# 04_FPGA_Bank500_Bank501.net
KiCad netlist of a schematic drawn in Altium Designer
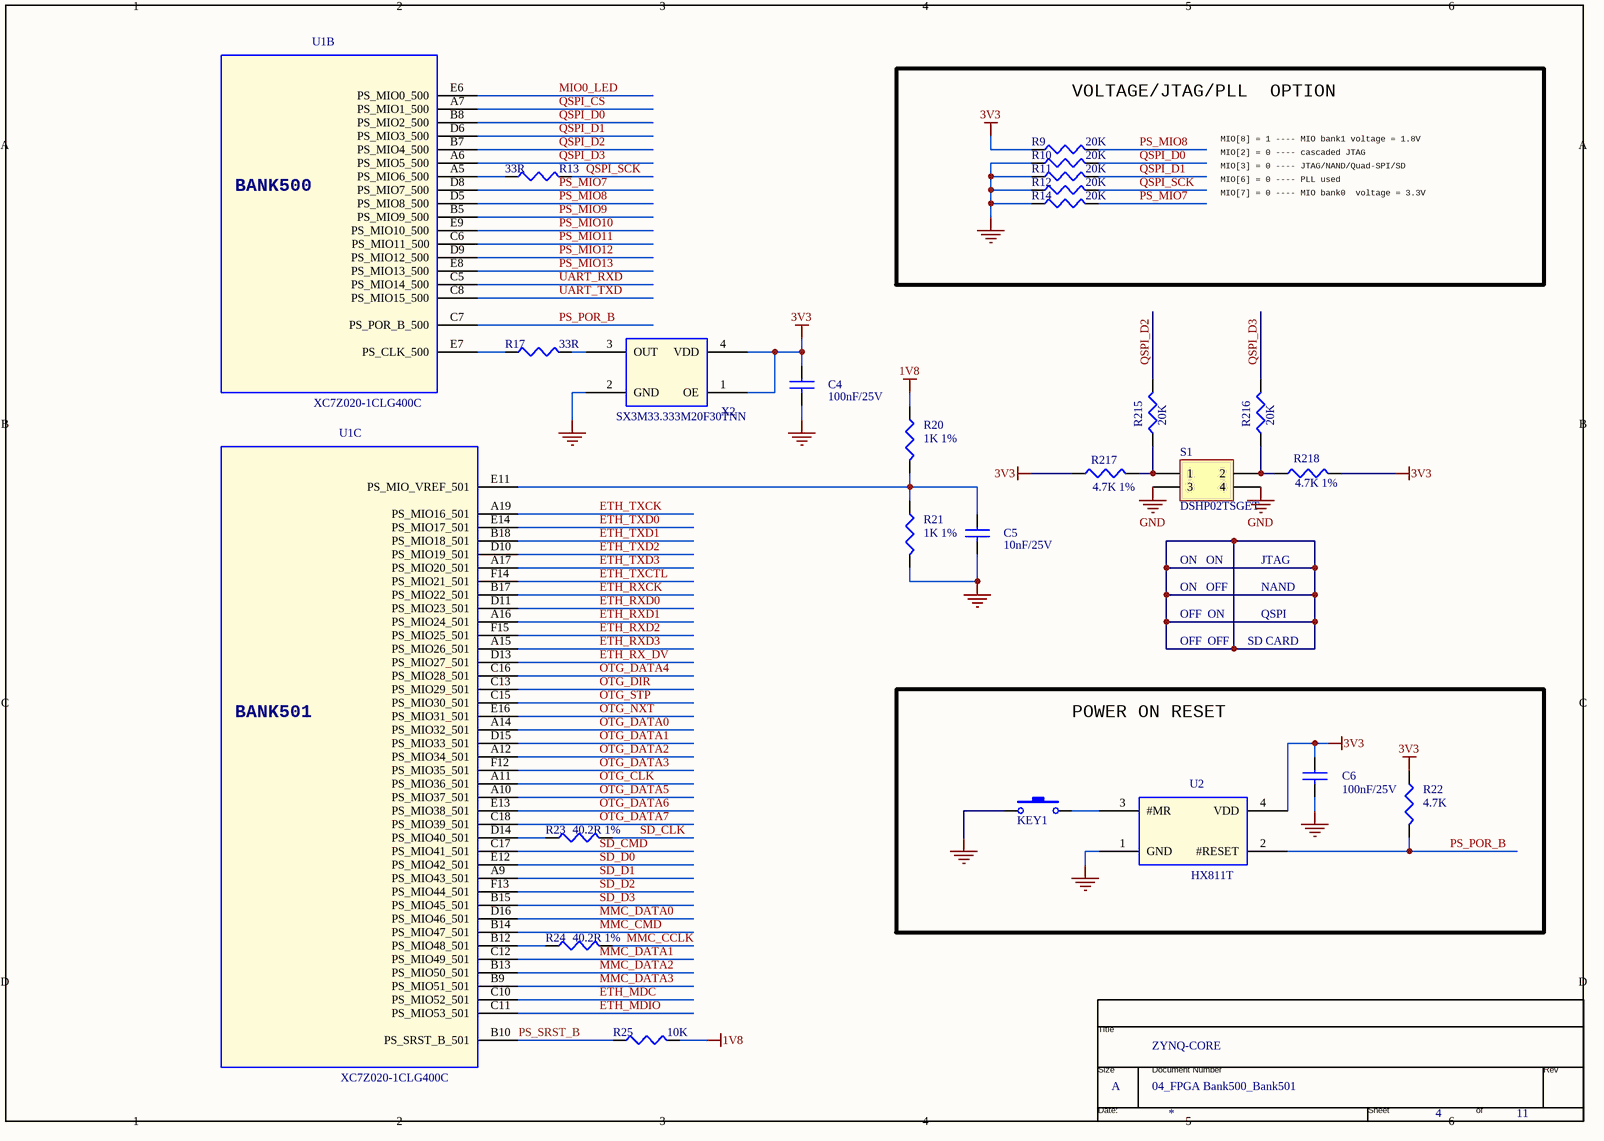
[diagram p0: 04_FPGA Bank500_Bank501.SchDoc]

(export (version "E")
  (design (tool "Eeschema 10.0.6"))
  (components
    (comp (ref "C4") (value "100nF/25V") (footprint "C0402") (libsource (lib "*") (part "CAP NP_Dup1")))
    (comp (ref "C5") (value "10nF/25V") (footprint "C0402") (libsource (lib "*") (part "CAP NP_Dup1")))
    (comp (ref "C6") (value "100nF/25V") (footprint "C0402") (libsource (lib "*") (part "CAP NP_Dup1")))
    (comp (ref "KEY1")
      (value "TS-1071AD-A1B3-D4")
      (footprint "KEY_3*4*2")
      (libsource (lib "AD库工程--FEIGE") (part "switch-anniu"))
    )
    (comp (ref "R9") (value "20K") (footprint "R0402") (libsource (lib "*") (part "RESISTOR_Dup1")))
    (comp (ref "R10") (value "20K") (footprint "R0402") (libsource (lib "*") (part "RESISTOR_Dup1")))
    (comp (ref "R11") (value "20K") (footprint "R0402") (libsource (lib "*") (part "RESISTOR_Dup1")))
    (comp (ref "R12") (value "20K") (footprint "R0402") (libsource (lib "*") (part "RESISTOR_Dup1")))
    (comp (ref "R13") (value "33R") (footprint "R0402") (libsource (lib "*") (part "RESISTOR_Dup1")))
    (comp (ref "R14") (value "20K") (footprint "R0402") (libsource (lib "*") (part "RESISTOR_Dup1")))
    (comp (ref "R17") (value "33R") (footprint "R0402") (libsource (lib "*") (part "RESISTOR_Dup1")))
    (comp (ref "R20") (value "1K 1%") (footprint "R0402") (libsource (lib "*") (part "RESISTOR_Dup1")))
    (comp (ref "R21") (value "1K 1%") (footprint "R0402") (libsource (lib "*") (part "RESISTOR_Dup1")))
    (comp (ref "R22") (value "4.7K") (footprint "R0402") (libsource (lib "*") (part "RESISTOR_Dup1")))
    (comp (ref "R23") (value "40.2R 1%") (footprint "R0402") (libsource (lib "*") (part "RESISTOR_Dup1")))
    (comp (ref "R24") (value "40.2R 1%") (footprint "R0402") (libsource (lib "*") (part "RESISTOR_Dup1")))
    (comp (ref "R25") (value "10K") (footprint "R0402") (libsource (lib "*") (part "RESISTOR_Dup1")))
    (comp (ref "R215") (value "20K") (footprint "R0402") (libsource (lib "*") (part "RESISTOR_Dup1")))
    (comp (ref "R216") (value "20K") (footprint "R0402") (libsource (lib "*") (part "RESISTOR_Dup1")))
    (comp (ref "R217") (value "4.7K 1%") (footprint "R0402") (libsource (lib "*") (part "RESISTOR_Dup1")))
    (comp (ref "R218") (value "4.7K 1%") (footprint "R0402") (libsource (lib "*") (part "RESISTOR_Dup1")))
    (comp (ref "S1")
      (value "DSHP02TSGET")
      (footprint "KE-1.27-2Pin")
      (description "拨码开关")
      (fields (field (name "PUBLISHER") "Altium Limited"))
      (libsource (lib "Miscellaneous Connectors") (part "Header 2X2"))
    )
    (comp (ref "U1")
      (value "XC7Z020-1CLG400C")
      (footprint "CLG400")
      (libsource (lib "*") (part "Zynq7010/7020"))
    )
    (comp (ref "U2") (value "HX811T") (footprint "TCM811TERCTR") (libsource (lib "*") (part "TCM811TERCTR")))
    (comp (ref "X2")
      (value "SX3M33.333M20F30TNN")
      (footprint "OSC3_2X2_5")
      (libsource (lib "*") (part "crystal_active"))
    )
  )
  (nets
    (net (code "1") (name "/ETH_MDC") (class "Default")
      (node (ref "U1") (pin "C10") (pinfunction "PS_MIO52_501_C10") (pintype "passive"))
    )
    (net (code "2") (name "/ETH_MDIO") (class "Default")
      (node (ref "U1") (pin "C11") (pinfunction "PS_MIO53_501_C11") (pintype "passive"))
    )
    (net (code "3") (name "/ETH_RXCK") (class "Default")
      (node (ref "U1") (pin "B17") (pinfunction "PS_MIO22_501_B17") (pintype "passive"))
    )
    (net (code "4") (name "/ETH_RXD0") (class "Default")
      (node (ref "U1") (pin "D11") (pinfunction "PS_MIO23_501_D11") (pintype "passive"))
    )
    (net (code "5") (name "/ETH_RXD1") (class "Default")
      (node (ref "U1") (pin "A16") (pinfunction "PS_MIO24_501_A16") (pintype "passive"))
    )
    (net (code "6") (name "/ETH_RXD2") (class "Default")
      (node (ref "U1") (pin "F15") (pinfunction "PS_MIO25_501_F15") (pintype "passive"))
    )
    (net (code "7") (name "/ETH_RXD3") (class "Default")
      (node (ref "U1") (pin "A15") (pinfunction "PS_MIO26_501_A15") (pintype "passive"))
    )
    (net (code "8") (name "/ETH_RX_DV") (class "Default")
      (node (ref "U1") (pin "D13") (pinfunction "PS_MIO27_501_D13") (pintype "passive"))
    )
    (net (code "9") (name "/ETH_TXCK") (class "Default")
      (node (ref "U1") (pin "A19") (pinfunction "PS_MIO16_501_A19") (pintype "passive"))
    )
    (net (code "10") (name "/ETH_TXCTL") (class "Default")
      (node (ref "U1") (pin "F14") (pinfunction "PS_MIO21_501_F14") (pintype "passive"))
    )
    (net (code "11") (name "/ETH_TXD0") (class "Default")
      (node (ref "U1") (pin "E14") (pinfunction "PS_MIO17_501_E14") (pintype "passive"))
    )
    (net (code "12") (name "/ETH_TXD1") (class "Default")
      (node (ref "U1") (pin "B18") (pinfunction "PS_MIO18_501_B18") (pintype "passive"))
    )
    (net (code "13") (name "/ETH_TXD2") (class "Default")
      (node (ref "U1") (pin "D10") (pinfunction "PS_MIO19_501_D10") (pintype "passive"))
    )
    (net (code "14") (name "/ETH_TXD3") (class "Default")
      (node (ref "U1") (pin "A17") (pinfunction "PS_MIO20_501_A17") (pintype "passive"))
    )
    (net (code "15") (name "/MIO0_LED") (class "Default")
      (node (ref "U1") (pin "E6") (pinfunction "PS_MIO0_500_E6") (pintype "passive"))
    )
    (net (code "16") (name "/MMC_CCLK") (class "Default")
      (node (ref "R24") (pin "2") (pinfunction "2_2") (pintype "passive"))
    )
    (net (code "17") (name "/MMC_CMD") (class "Default")
      (node (ref "U1") (pin "B14") (pinfunction "PS_MIO47_501_B14") (pintype "passive"))
    )
    (net (code "18") (name "/MMC_DATA0") (class "Default")
      (node (ref "U1") (pin "D16") (pinfunction "PS_MIO46_501_D16") (pintype "passive"))
    )
    (net (code "19") (name "/MMC_DATA1") (class "Default")
      (node (ref "U1") (pin "C12") (pinfunction "PS_MIO49_501_C12") (pintype "passive"))
    )
    (net (code "20") (name "/MMC_DATA2") (class "Default")
      (node (ref "U1") (pin "B13") (pinfunction "PS_MIO50_501_B13") (pintype "passive"))
    )
    (net (code "21") (name "/MMC_DATA3") (class "Default")
      (node (ref "U1") (pin "B9") (pinfunction "PS_MIO51_501_B9") (pintype "passive"))
    )
    (net (code "22") (name "/OTG_CLK") (class "Default")
      (node (ref "U1") (pin "A11") (pinfunction "PS_MIO36_501_A11") (pintype "passive"))
    )
    (net (code "23") (name "/OTG_DATA0") (class "Default")
      (node (ref "U1") (pin "A14") (pinfunction "PS_MIO32_501_A14") (pintype "passive"))
    )
    (net (code "24") (name "/OTG_DATA1") (class "Default")
      (node (ref "U1") (pin "D15") (pinfunction "PS_MIO33_501_D15") (pintype "passive"))
    )
    (net (code "25") (name "/OTG_DATA2") (class "Default")
      (node (ref "U1") (pin "A12") (pinfunction "PS_MIO34_501_A12") (pintype "passive"))
    )
    (net (code "26") (name "/OTG_DATA3") (class "Default")
      (node (ref "U1") (pin "F12") (pinfunction "PS_MIO35_501_F12") (pintype "passive"))
    )
    (net (code "27") (name "/OTG_DATA4") (class "Default")
      (node (ref "U1") (pin "C16") (pinfunction "PS_MIO28_501_C16") (pintype "passive"))
    )
    (net (code "28") (name "/OTG_DATA5") (class "Default")
      (node (ref "U1") (pin "A10") (pinfunction "PS_MIO37_501_A10") (pintype "passive"))
    )
    (net (code "29") (name "/OTG_DATA6") (class "Default")
      (node (ref "U1") (pin "E13") (pinfunction "PS_MIO38_501_E13") (pintype "passive"))
    )
    (net (code "30") (name "/OTG_DATA7") (class "Default")
      (node (ref "U1") (pin "C18") (pinfunction "PS_MIO39_501_C18") (pintype "passive"))
    )
    (net (code "31") (name "/OTG_DIR") (class "Default")
      (node (ref "U1") (pin "C13") (pinfunction "PS_MIO29_501_C13") (pintype "passive"))
    )
    (net (code "32") (name "/OTG_NXT") (class "Default")
      (node (ref "U1") (pin "E16") (pinfunction "PS_MIO31_501_E16") (pintype "passive"))
    )
    (net (code "33") (name "/OTG_STP") (class "Default")
      (node (ref "U1") (pin "C15") (pinfunction "PS_MIO30_501_C15") (pintype "passive"))
    )
    (net (code "34") (name "/PS_MIO7") (class "Default")
      (node (ref "R14") (pin "2") (pinfunction "2_2") (pintype "passive"))
      (node (ref "U1") (pin "D8") (pinfunction "PS_MIO7_500_D8") (pintype "passive"))
    )
    (net (code "35") (name "/PS_MIO8") (class "Default")
      (node (ref "R9") (pin "2") (pinfunction "2_2") (pintype "passive"))
      (node (ref "U1") (pin "D5") (pinfunction "PS_MIO8_500_D5") (pintype "passive"))
    )
    (net (code "36") (name "/PS_MIO9") (class "Default")
      (node (ref "U1") (pin "B5") (pinfunction "PS_MIO9_500_B5") (pintype "passive"))
    )
    (net (code "37") (name "/PS_MIO10") (class "Default")
      (node (ref "U1") (pin "E9") (pinfunction "PS_MIO10_500_E9") (pintype "passive"))
    )
    (net (code "38") (name "/PS_MIO11") (class "Default")
      (node (ref "U1") (pin "C6") (pinfunction "PS_MIO11_500_C6") (pintype "passive"))
    )
    (net (code "39") (name "/PS_MIO12") (class "Default")
      (node (ref "U1") (pin "D9") (pinfunction "PS_MIO12_500_D9") (pintype "passive"))
    )
    (net (code "40") (name "/PS_MIO13") (class "Default")
      (node (ref "U1") (pin "E8") (pinfunction "PS_MIO13_500_E8") (pintype "passive"))
    )
    (net (code "41") (name "/PS_POR_B") (class "Default")
      (node (ref "R22") (pin "2") (pinfunction "2_2") (pintype "passive"))
      (node (ref "U1") (pin "C7") (pinfunction "PS_POR_B_500_C7") (pintype "passive"))
      (node (ref "U2") (pin "2") (pinfunction "#RESET_2") (pintype "passive"))
    )
    (net (code "42") (name "/PS_SRST_B") (class "Default")
      (node (ref "R25") (pin "1") (pinfunction "1_1") (pintype "passive"))
      (node (ref "U1") (pin "B10") (pinfunction "PS_SRST_B_501_B10") (pintype "passive"))
    )
    (net (code "43") (name "/QSPI_CS") (class "Default")
      (node (ref "U1") (pin "A7") (pinfunction "PS_MIO1_500_A7") (pintype "passive"))
    )
    (net (code "44") (name "/QSPI_D0") (class "Default")
      (node (ref "R10") (pin "2") (pinfunction "2_2") (pintype "passive"))
      (node (ref "U1") (pin "B8") (pinfunction "PS_MIO2_500_B8") (pintype "passive"))
    )
    (net (code "45") (name "/QSPI_D1") (class "Default")
      (node (ref "R11") (pin "2") (pinfunction "2_2") (pintype "passive"))
      (node (ref "U1") (pin "D6") (pinfunction "PS_MIO3_500_D6") (pintype "passive"))
    )
    (net (code "46") (name "/QSPI_D2") (class "Default")
      (node (ref "R215") (pin "2") (pinfunction "2_2") (pintype "passive"))
      (node (ref "U1") (pin "B7") (pinfunction "PS_MIO4_500_B7") (pintype "passive"))
    )
    (net (code "47") (name "/QSPI_D3") (class "Default")
      (node (ref "R216") (pin "2") (pinfunction "2_2") (pintype "passive"))
      (node (ref "U1") (pin "A6") (pinfunction "PS_MIO5_500_A6") (pintype "passive"))
    )
    (net (code "48") (name "/QSPI_SCK") (class "Default")
      (node (ref "R12") (pin "2") (pinfunction "2_2") (pintype "passive"))
      (node (ref "R13") (pin "2") (pinfunction "2_2") (pintype "passive"))
    )
    (net (code "49") (name "/SD_CLK") (class "Default")
      (node (ref "R23") (pin "2") (pinfunction "2_2") (pintype "passive"))
    )
    (net (code "50") (name "/SD_CMD") (class "Default")
      (node (ref "U1") (pin "C17") (pinfunction "PS_MIO41_501_C17") (pintype "passive"))
    )
    (net (code "51") (name "/SD_D0") (class "Default")
      (node (ref "U1") (pin "E12") (pinfunction "PS_MIO42_501_E12") (pintype "passive"))
    )
    (net (code "52") (name "/SD_D1") (class "Default")
      (node (ref "U1") (pin "A9") (pinfunction "PS_MIO43_501_A9") (pintype "passive"))
    )
    (net (code "53") (name "/SD_D2") (class "Default")
      (node (ref "U1") (pin "F13") (pinfunction "PS_MIO44_501_F13") (pintype "passive"))
    )
    (net (code "54") (name "/SD_D3") (class "Default")
      (node (ref "U1") (pin "B15") (pinfunction "PS_MIO45_501_B15") (pintype "passive"))
    )
    (net (code "55") (name "/UART_RXD") (class "Default")
      (node (ref "U1") (pin "C5") (pinfunction "PS_MIO14_500_C5") (pintype "passive"))
    )
    (net (code "56") (name "/UART_TXD") (class "Default")
      (node (ref "U1") (pin "C8") (pinfunction "PS_MIO15_500_C8") (pintype "passive"))
    )
    (net (code "57") (name "1V8") (class "Default")
      (node (ref "R20") (pin "1") (pinfunction "1_1") (pintype "passive"))
      (node (ref "R25") (pin "2") (pinfunction "2_2") (pintype "passive"))
    )
    (net (code "58") (name "3V3") (class "Default")
      (node (ref "C4") (pin "1") (pinfunction "1_1") (pintype "passive"))
      (node (ref "C6") (pin "1") (pinfunction "1_1") (pintype "passive"))
      (node (ref "R217") (pin "1") (pinfunction "1_1") (pintype "passive"))
      (node (ref "R218") (pin "2") (pinfunction "2_2") (pintype "passive"))
      (node (ref "R22") (pin "1") (pinfunction "1_1") (pintype "passive"))
      (node (ref "R9") (pin "1") (pinfunction "1_1") (pintype "passive"))
      (node (ref "U2") (pin "4") (pinfunction "VDD_4") (pintype "passive"))
      (node (ref "X2") (pin "1") (pinfunction "OE_1") (pintype "passive"))
      (node (ref "X2") (pin "4") (pinfunction "VDD_4") (pintype "passive"))
    )
    (net (code "59") (name "GND") (class "Default")
      (node (ref "C4") (pin "2") (pinfunction "2_2") (pintype "passive"))
      (node (ref "C5") (pin "2") (pinfunction "2_2") (pintype "passive"))
      (node (ref "C6") (pin "2") (pinfunction "2_2") (pintype "passive"))
      (node (ref "KEY1") (pin "1") (pinfunction "1_1") (pintype "passive"))
      (node (ref "R10") (pin "1") (pinfunction "1_1") (pintype "passive"))
      (node (ref "R11") (pin "1") (pinfunction "1_1") (pintype "passive"))
      (node (ref "R12") (pin "1") (pinfunction "1_1") (pintype "passive"))
      (node (ref "R14") (pin "1") (pinfunction "1_1") (pintype "passive"))
      (node (ref "R21") (pin "2") (pinfunction "2_2") (pintype "passive"))
      (node (ref "S1") (pin "3") (pinfunction "3_3") (pintype "passive"))
      (node (ref "S1") (pin "4") (pinfunction "4_4") (pintype "passive"))
      (node (ref "U2") (pin "1") (pinfunction "GND_1") (pintype "passive"))
      (node (ref "X2") (pin "2") (pinfunction "GND_2") (pintype "passive"))
    )
    (net (code "60") (name "Net-(R215-Pad1)") (class "Default")
      (node (ref "R215") (pin "1") (pinfunction "1_1") (pintype "passive"))
      (node (ref "R217") (pin "2") (pinfunction "2_2") (pintype "passive"))
      (node (ref "S1") (pin "1") (pinfunction "1_1") (pintype "passive"))
    )
    (net (code "61") (name "Net-(R216-Pad1)") (class "Default")
      (node (ref "R216") (pin "1") (pinfunction "1_1") (pintype "passive"))
      (node (ref "R218") (pin "1") (pinfunction "1_1") (pintype "passive"))
      (node (ref "S1") (pin "2") (pinfunction "2_2") (pintype "passive"))
    )
    (net (code "62") (name "Net-(U1B-PS_CLK_500)") (class "Default")
      (node (ref "R17") (pin "1") (pinfunction "1_1") (pintype "passive"))
      (node (ref "U1") (pin "E7") (pinfunction "PS_CLK_500_E7") (pintype "passive"))
    )
    (net (code "63") (name "Net-(U1B-PS_MIO6_500)") (class "Default")
      (node (ref "R13") (pin "1") (pinfunction "1_1") (pintype "passive"))
      (node (ref "U1") (pin "A5") (pinfunction "PS_MIO6_500_A5") (pintype "passive"))
    )
    (net (code "64") (name "Net-(U1C-PS_MIO40_501)") (class "Default")
      (node (ref "R23") (pin "1") (pinfunction "1_1") (pintype "passive"))
      (node (ref "U1") (pin "D14") (pinfunction "PS_MIO40_501_D14") (pintype "passive"))
    )
    (net (code "65") (name "Net-(U1C-PS_MIO48_501)") (class "Default")
      (node (ref "R24") (pin "1") (pinfunction "1_1") (pintype "passive"))
      (node (ref "U1") (pin "B12") (pinfunction "PS_MIO48_501_B12") (pintype "passive"))
    )
    (net (code "66") (name "Net-(U1C-PS_MIO_VREF_501)") (class "Default")
      (node (ref "C5") (pin "1") (pinfunction "1_1") (pintype "passive"))
      (node (ref "R20") (pin "2") (pinfunction "2_2") (pintype "passive"))
      (node (ref "R21") (pin "1") (pinfunction "1_1") (pintype "passive"))
      (node (ref "U1") (pin "E11") (pinfunction "PS_MIO_VREF_501_E11") (pintype "passive"))
    )
    (net (code "67") (name "Net-(U2-#MR)") (class "Default")
      (node (ref "KEY1") (pin "2") (pinfunction "2_2") (pintype "passive"))
      (node (ref "U2") (pin "3") (pinfunction "#MR_3") (pintype "passive"))
    )
    (net (code "68") (name "Net-(X2-OUT)") (class "Default")
      (node (ref "R17") (pin "2") (pinfunction "2_2") (pintype "passive"))
      (node (ref "X2") (pin "3") (pinfunction "OUT_3") (pintype "passive"))
    )
  )
)
